# Connect.net
KiCad netlist of a schematic drawn in Altium Designer
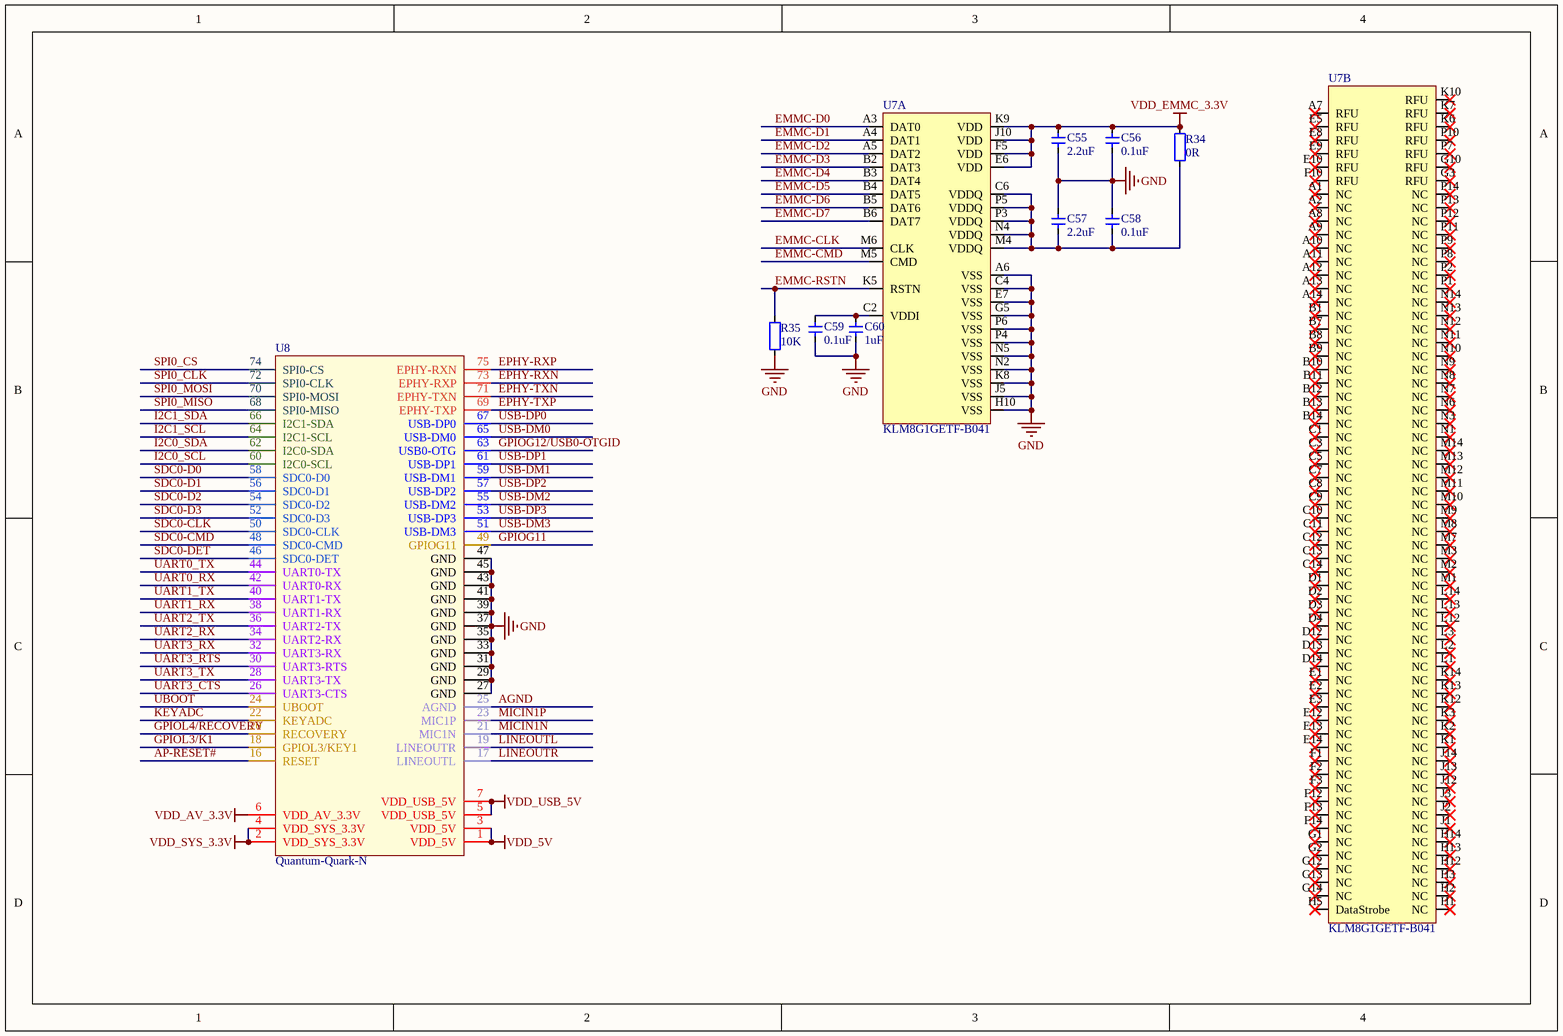
[diagram p0: Connect.SchDoc]

(export (version "E")
  (design (tool "Eeschema 10.0.6"))
  (components
    (comp (ref "C55")
      (value "2.2uF")
      (footprint "CAP_0402")
      (description "Capacitor")
      (libsource (lib "MyPcbLib") (part "电容-0402"))
    )
    (comp (ref "C56")
      (value "0.1uF")
      (footprint "CAP_0402")
      (description "Capacitor")
      (libsource (lib "MyPcbLib") (part "电容-0402"))
    )
    (comp (ref "C57")
      (value "2.2uF")
      (footprint "CAP_0402")
      (description "Capacitor")
      (libsource (lib "MyPcbLib") (part "电容-0402"))
    )
    (comp (ref "C58")
      (value "0.1uF")
      (footprint "CAP_0402")
      (description "Capacitor")
      (libsource (lib "MyPcbLib") (part "电容-0402"))
    )
    (comp (ref "C59")
      (value "0.1uF")
      (footprint "CAP_0402")
      (description "Capacitor")
      (libsource (lib "MyPcbLib") (part "电容-0402"))
    )
    (comp (ref "C60")
      (value "1uF")
      (footprint "CAP_0402")
      (description "Capacitor")
      (libsource (lib "MyPcbLib") (part "电容-0402"))
    )
    (comp (ref "R34")
      (value "0R")
      (footprint "RES_0402")
      (description "Resistor")
      (libsource (lib "MyPcbLib") (part "电阻-0402"))
    )
    (comp (ref "R35")
      (value "10K")
      (footprint "RES_0402")
      (description "Resistor")
      (libsource (lib "") (part "电阻-0402_1"))
    )
    (comp (ref "U7")
      (value "KLM8G1GETF-B041")
      (footprint "FBGA153")
      (description "8GB三星EMMC芯片")
      (libsource (lib "MxM") (part "EMMC"))
    )
    (comp (ref "U8")
      (value "Quantum-Quark-N")
      (footprint "M.2")
      (libsource (lib "MxM") (part "Quantum-Quark-N"))
    )
  )
  (nets
    (net (code "1") (name "/AGND") (class "Default")
      (node (ref "U8") (pin "25") (pinfunction "AGND_25") (pintype "passive"))
    )
    (net (code "2") (name "/AP-RESET#") (class "Default")
      (node (ref "U8") (pin "16") (pinfunction "RESET_16") (pintype "passive"))
    )
    (net (code "3") (name "/EMMC-CLK") (class "Default")
      (node (ref "U7") (pin "M6") (pinfunction "CLK_M6") (pintype "passive"))
    )
    (net (code "4") (name "/EMMC-CMD") (class "Default")
      (node (ref "U7") (pin "M5") (pinfunction "CMD_M5") (pintype "passive"))
    )
    (net (code "5") (name "/EMMC-D0") (class "Default")
      (node (ref "U7") (pin "A3") (pinfunction "DAT0_A3") (pintype "passive"))
    )
    (net (code "6") (name "/EMMC-D1") (class "Default")
      (node (ref "U7") (pin "A4") (pinfunction "DAT1_A4") (pintype "passive"))
    )
    (net (code "7") (name "/EMMC-D2") (class "Default")
      (node (ref "U7") (pin "A5") (pinfunction "DAT2_A5") (pintype "passive"))
    )
    (net (code "8") (name "/EMMC-D3") (class "Default")
      (node (ref "U7") (pin "B2") (pinfunction "DAT3_B2") (pintype "passive"))
    )
    (net (code "9") (name "/EMMC-D4") (class "Default")
      (node (ref "U7") (pin "B3") (pinfunction "DAT4_B3") (pintype "passive"))
    )
    (net (code "10") (name "/EMMC-D5") (class "Default")
      (node (ref "U7") (pin "B4") (pinfunction "DAT5_B4") (pintype "passive"))
    )
    (net (code "11") (name "/EMMC-D6") (class "Default")
      (node (ref "U7") (pin "B5") (pinfunction "DAT6_B5") (pintype "passive"))
    )
    (net (code "12") (name "/EMMC-D7") (class "Default")
      (node (ref "U7") (pin "B6") (pinfunction "DAT7_B6") (pintype "passive"))
    )
    (net (code "13") (name "/EMMC-RSTN") (class "Default")
      (node (ref "R35") (pin "2") (pinfunction "2_2") (pintype "passive"))
      (node (ref "U7") (pin "K5") (pinfunction "RSTN_K5") (pintype "passive"))
    )
    (net (code "14") (name "/EPHY-RXN") (class "Default")
      (node (ref "U8") (pin "73") (pinfunction "EPHY-RXP_73") (pintype "passive"))
    )
    (net (code "15") (name "/EPHY-RXP") (class "Default")
      (node (ref "U8") (pin "75") (pinfunction "EPHY-RXN_75") (pintype "passive"))
    )
    (net (code "16") (name "/EPHY-TXN") (class "Default")
      (node (ref "U8") (pin "71") (pinfunction "EPHY-TXN_71") (pintype "passive"))
    )
    (net (code "17") (name "/EPHY-TXP") (class "Default")
      (node (ref "U8") (pin "69") (pinfunction "EPHY-TXP_69") (pintype "passive"))
    )
    (net (code "18") (name "/GPIOG11") (class "Default")
      (node (ref "U8") (pin "49") (pinfunction "GPIOG11_49") (pintype "passive"))
    )
    (net (code "19") (name "/GPIOG12{slash}USB0-OTGID") (class "Default")
      (node (ref "U8") (pin "63") (pinfunction "USB0-OTG_63") (pintype "passive"))
    )
    (net (code "20") (name "/GPIOL3{slash}K1") (class "Default")
      (node (ref "U8") (pin "18") (pinfunction "GPIOL3/KEY1_18") (pintype "passive"))
    )
    (net (code "21") (name "/GPIOL4{slash}RECOVERY") (class "Default")
      (node (ref "U8") (pin "20") (pinfunction "RECOVERY_20") (pintype "passive"))
    )
    (net (code "22") (name "/I2C0_SCL") (class "Default")
      (node (ref "U8") (pin "60") (pinfunction "I2C0-SCL_60") (pintype "passive"))
    )
    (net (code "23") (name "/I2C0_SDA") (class "Default")
      (node (ref "U8") (pin "62") (pinfunction "I2C0-SDA_62") (pintype "passive"))
    )
    (net (code "24") (name "/I2C1_SCL") (class "Default")
      (node (ref "U8") (pin "64") (pinfunction "I2C1-SCL_64") (pintype "passive"))
    )
    (net (code "25") (name "/I2C1_SDA") (class "Default")
      (node (ref "U8") (pin "66") (pinfunction "I2C1-SDA_66") (pintype "passive"))
    )
    (net (code "26") (name "/KEYADC") (class "Default")
      (node (ref "U8") (pin "22") (pinfunction "KEYADC_22") (pintype "passive"))
    )
    (net (code "27") (name "/LINEOUTL") (class "Default")
      (node (ref "U8") (pin "19") (pinfunction "LINEOUTR_19") (pintype "passive"))
    )
    (net (code "28") (name "/LINEOUTR") (class "Default")
      (node (ref "U8") (pin "17") (pinfunction "LINEOUTL_17") (pintype "passive"))
    )
    (net (code "29") (name "/MICIN1N") (class "Default")
      (node (ref "U8") (pin "21") (pinfunction "MIC1N_21") (pintype "passive"))
    )
    (net (code "30") (name "/MICIN1P") (class "Default")
      (node (ref "U8") (pin "23") (pinfunction "MIC1P_23") (pintype "passive"))
    )
    (net (code "31") (name "/SDC0-CLK") (class "Default")
      (node (ref "U8") (pin "50") (pinfunction "SDC0-CLK_50") (pintype "passive"))
    )
    (net (code "32") (name "/SDC0-CMD") (class "Default")
      (node (ref "U8") (pin "48") (pinfunction "SDC0-CMD_48") (pintype "passive"))
    )
    (net (code "33") (name "/SDC0-D0") (class "Default")
      (node (ref "U8") (pin "58") (pinfunction "SDC0-D0_58") (pintype "passive"))
    )
    (net (code "34") (name "/SDC0-D1") (class "Default")
      (node (ref "U8") (pin "56") (pinfunction "SDC0-D1_56") (pintype "passive"))
    )
    (net (code "35") (name "/SDC0-D2") (class "Default")
      (node (ref "U8") (pin "54") (pinfunction "SDC0-D2_54") (pintype "passive"))
    )
    (net (code "36") (name "/SDC0-D3") (class "Default")
      (node (ref "U8") (pin "52") (pinfunction "SDC0-D3_52") (pintype "passive"))
    )
    (net (code "37") (name "/SDC0-DET") (class "Default")
      (node (ref "U8") (pin "46") (pinfunction "SDC0-DET_46") (pintype "passive"))
    )
    (net (code "38") (name "/SPI0_CLK") (class "Default")
      (node (ref "U8") (pin "72") (pinfunction "SPI0-CLK_72") (pintype "passive"))
    )
    (net (code "39") (name "/SPI0_CS") (class "Default")
      (node (ref "U8") (pin "74") (pinfunction "SPI0-CS_74") (pintype "passive"))
    )
    (net (code "40") (name "/SPI0_MISO") (class "Default")
      (node (ref "U8") (pin "68") (pinfunction "SPI0-MISO_68") (pintype "passive"))
    )
    (net (code "41") (name "/SPI0_MOSI") (class "Default")
      (node (ref "U8") (pin "70") (pinfunction "SPI0-MOSI_70") (pintype "passive"))
    )
    (net (code "42") (name "/UART0_RX") (class "Default")
      (node (ref "U8") (pin "42") (pinfunction "UART0-RX_42") (pintype "passive"))
    )
    (net (code "43") (name "/UART0_TX") (class "Default")
      (node (ref "U8") (pin "44") (pinfunction "UART0-TX_44") (pintype "passive"))
    )
    (net (code "44") (name "/UART1_RX") (class "Default")
      (node (ref "U8") (pin "38") (pinfunction "UART1-RX_38") (pintype "passive"))
    )
    (net (code "45") (name "/UART1_TX") (class "Default")
      (node (ref "U8") (pin "40") (pinfunction "UART1-TX_40") (pintype "passive"))
    )
    (net (code "46") (name "/UART2_RX") (class "Default")
      (node (ref "U8") (pin "34") (pinfunction "UART2-RX_34") (pintype "passive"))
    )
    (net (code "47") (name "/UART2_TX") (class "Default")
      (node (ref "U8") (pin "36") (pinfunction "UART2-TX_36") (pintype "passive"))
    )
    (net (code "48") (name "/UART3_CTS") (class "Default")
      (node (ref "U8") (pin "26") (pinfunction "UART3-CTS_26") (pintype "passive"))
    )
    (net (code "49") (name "/UART3_RTS") (class "Default")
      (node (ref "U8") (pin "30") (pinfunction "UART3-RTS_30") (pintype "passive"))
    )
    (net (code "50") (name "/UART3_RX") (class "Default")
      (node (ref "U8") (pin "32") (pinfunction "UART3-RX_32") (pintype "passive"))
    )
    (net (code "51") (name "/UART3_TX") (class "Default")
      (node (ref "U8") (pin "28") (pinfunction "UART3-TX_28") (pintype "passive"))
    )
    (net (code "52") (name "/UBOOT") (class "Default")
      (node (ref "U8") (pin "24") (pinfunction "UBOOT_24") (pintype "passive"))
    )
    (net (code "53") (name "/USB-DM0") (class "Default")
      (node (ref "U8") (pin "65") (pinfunction "USB-DM0_65") (pintype "passive"))
    )
    (net (code "54") (name "/USB-DM1") (class "Default")
      (node (ref "U8") (pin "59") (pinfunction "USB-DM1_59") (pintype "passive"))
    )
    (net (code "55") (name "/USB-DM2") (class "Default")
      (node (ref "U8") (pin "55") (pinfunction "USB-DM2_55") (pintype "passive"))
    )
    (net (code "56") (name "/USB-DM3") (class "Default")
      (node (ref "U8") (pin "51") (pinfunction "USB-DM3_51") (pintype "passive"))
    )
    (net (code "57") (name "/USB-DP0") (class "Default")
      (node (ref "U8") (pin "67") (pinfunction "USB-DP0_67") (pintype "passive"))
    )
    (net (code "58") (name "/USB-DP1") (class "Default")
      (node (ref "U8") (pin "61") (pinfunction "USB-DP1_61") (pintype "passive"))
    )
    (net (code "59") (name "/USB-DP2") (class "Default")
      (node (ref "U8") (pin "57") (pinfunction "USB-DP2_57") (pintype "passive"))
    )
    (net (code "60") (name "/USB-DP3") (class "Default")
      (node (ref "U8") (pin "53") (pinfunction "USB-DP3_53") (pintype "passive"))
    )
    (net (code "61") (name "GND") (class "Default")
      (node (ref "C55") (pin "1") (pinfunction "1_1") (pintype "passive"))
      (node (ref "C56") (pin "1") (pinfunction "1_1") (pintype "passive"))
      (node (ref "C57") (pin "2") (pinfunction "2_2") (pintype "passive"))
      (node (ref "C58") (pin "2") (pinfunction "2_2") (pintype "passive"))
      (node (ref "C59") (pin "1") (pinfunction "1_1") (pintype "passive"))
      (node (ref "C60") (pin "1") (pinfunction "1_1") (pintype "passive"))
      (node (ref "R35") (pin "1") (pinfunction "1_1") (pintype "passive"))
      (node (ref "U7") (pin "A6") (pinfunction "VSS_A6") (pintype "passive"))
      (node (ref "U7") (pin "C4") (pinfunction "VSS_C4") (pintype "passive"))
      (node (ref "U7") (pin "E7") (pinfunction "VSS_E7") (pintype "passive"))
      (node (ref "U7") (pin "G5") (pinfunction "VSS_G5") (pintype "passive"))
      (node (ref "U7") (pin "H10") (pinfunction "VSS_H10") (pintype "passive"))
      (node (ref "U7") (pin "J5") (pinfunction "VSS_J5") (pintype "passive"))
      (node (ref "U7") (pin "K8") (pinfunction "VSS_K8") (pintype "passive"))
      (node (ref "U7") (pin "N2") (pinfunction "VSS_N2") (pintype "passive"))
      (node (ref "U7") (pin "N5") (pinfunction "VSS_N5") (pintype "passive"))
      (node (ref "U7") (pin "P4") (pinfunction "VSS_P4") (pintype "passive"))
      (node (ref "U7") (pin "P6") (pinfunction "VSS_P6") (pintype "passive"))
      (node (ref "U8") (pin "27") (pinfunction "GND_27") (pintype "passive"))
      (node (ref "U8") (pin "29") (pinfunction "GND_29") (pintype "passive"))
      (node (ref "U8") (pin "31") (pinfunction "GND_31") (pintype "passive"))
      (node (ref "U8") (pin "33") (pinfunction "GND_33") (pintype "passive"))
      (node (ref "U8") (pin "35") (pinfunction "GND_35") (pintype "passive"))
      (node (ref "U8") (pin "37") (pinfunction "GND_37") (pintype "passive"))
      (node (ref "U8") (pin "39") (pinfunction "GND_39") (pintype "passive"))
      (node (ref "U8") (pin "41") (pinfunction "GND_41") (pintype "passive"))
      (node (ref "U8") (pin "43") (pinfunction "GND_43") (pintype "passive"))
      (node (ref "U8") (pin "45") (pinfunction "GND_45") (pintype "passive"))
      (node (ref "U8") (pin "47") (pinfunction "GND_47") (pintype "passive"))
    )
    (net (code "62") (name "Net-(C57-Pad1)") (class "Default")
      (node (ref "C57") (pin "1") (pinfunction "1_1") (pintype "passive"))
      (node (ref "C58") (pin "1") (pinfunction "1_1") (pintype "passive"))
      (node (ref "R34") (pin "2") (pinfunction "2_2") (pintype "passive"))
      (node (ref "U7") (pin "C6") (pinfunction "VDDQ_C6") (pintype "passive"))
      (node (ref "U7") (pin "M4") (pinfunction "VDDQ_M4") (pintype "passive"))
      (node (ref "U7") (pin "N4") (pinfunction "VDDQ_N4") (pintype "passive"))
      (node (ref "U7") (pin "P3") (pinfunction "VDDQ_P3") (pintype "passive"))
      (node (ref "U7") (pin "P5") (pinfunction "VDDQ_P5") (pintype "passive"))
    )
    (net (code "63") (name "Net-(U7A-VDDI)") (class "Default")
      (node (ref "C59") (pin "2") (pinfunction "2_2") (pintype "passive"))
      (node (ref "C60") (pin "2") (pinfunction "2_2") (pintype "passive"))
      (node (ref "U7") (pin "C2") (pinfunction "VDDI_C2") (pintype "passive"))
    )
    (net (code "64") (name "VDD_5V") (class "Default")
      (node (ref "U8") (pin "1") (pinfunction "VDD_5V_1") (pintype "passive"))
      (node (ref "U8") (pin "3") (pinfunction "VDD_5V_3") (pintype "passive"))
    )
    (net (code "65") (name "VDD_AV_3.3V") (class "Default")
      (node (ref "U8") (pin "6") (pinfunction "VDD_AV_3.3V_6") (pintype "passive"))
    )
    (net (code "66") (name "VDD_EMMC_3.3V") (class "Default")
      (node (ref "C55") (pin "2") (pinfunction "2_2") (pintype "passive"))
      (node (ref "C56") (pin "2") (pinfunction "2_2") (pintype "passive"))
      (node (ref "R34") (pin "1") (pinfunction "1_1") (pintype "passive"))
      (node (ref "U7") (pin "E6") (pinfunction "VDD_E6") (pintype "passive"))
      (node (ref "U7") (pin "F5") (pinfunction "VDD_F5") (pintype "passive"))
      (node (ref "U7") (pin "J10") (pinfunction "VDD_J10") (pintype "passive"))
      (node (ref "U7") (pin "K9") (pinfunction "VDD_K9") (pintype "passive"))
    )
    (net (code "67") (name "VDD_SYS_3.3V") (class "Default")
      (node (ref "U8") (pin "2") (pinfunction "VDD_SYS_3.3V_2") (pintype "passive"))
      (node (ref "U8") (pin "4") (pinfunction "VDD_SYS_3.3V_4") (pintype "passive"))
    )
    (net (code "68") (name "VDD_USB_5V") (class "Default")
      (node (ref "U8") (pin "5") (pinfunction "VDD_USB_5V_5") (pintype "passive"))
      (node (ref "U8") (pin "7") (pinfunction "VDD_USB_5V_7") (pintype "passive"))
    )
    (net (code "69") (name "unconnected-(U7B-DataStrobe-PadH5)") (class "Default")
      (node (ref "U7") (pin "H5") (pinfunction "DataStrobe_H5") (pintype "passive+no_connect"))
    )
    (net (code "70") (name "unconnected-(U7B-NC-PadA1)") (class "Default")
      (node (ref "U7") (pin "A1") (pinfunction "NC_A1") (pintype "passive+no_connect"))
    )
    (net (code "71") (name "unconnected-(U7B-NC-PadA2)") (class "Default")
      (node (ref "U7") (pin "A2") (pinfunction "NC_A2") (pintype "passive+no_connect"))
    )
    (net (code "72") (name "unconnected-(U7B-NC-PadA8)") (class "Default")
      (node (ref "U7") (pin "A8") (pinfunction "NC_A8") (pintype "passive+no_connect"))
    )
    (net (code "73") (name "unconnected-(U7B-NC-PadA9)") (class "Default")
      (node (ref "U7") (pin "A9") (pinfunction "NC_A9") (pintype "passive+no_connect"))
    )
    (net (code "74") (name "unconnected-(U7B-NC-PadA10)") (class "Default")
      (node (ref "U7") (pin "A10") (pinfunction "NC_A10") (pintype "passive+no_connect"))
    )
    (net (code "75") (name "unconnected-(U7B-NC-PadA11)") (class "Default")
      (node (ref "U7") (pin "A11") (pinfunction "NC_A11") (pintype "passive+no_connect"))
    )
    (net (code "76") (name "unconnected-(U7B-NC-PadA12)") (class "Default")
      (node (ref "U7") (pin "A12") (pinfunction "NC_A12") (pintype "passive+no_connect"))
    )
    (net (code "77") (name "unconnected-(U7B-NC-PadA13)") (class "Default")
      (node (ref "U7") (pin "A13") (pinfunction "NC_A13") (pintype "passive+no_connect"))
    )
    (net (code "78") (name "unconnected-(U7B-NC-PadA14)") (class "Default")
      (node (ref "U7") (pin "A14") (pinfunction "NC_A14") (pintype "passive+no_connect"))
    )
    (net (code "79") (name "unconnected-(U7B-NC-PadB1)") (class "Default")
      (node (ref "U7") (pin "B1") (pinfunction "NC_B1") (pintype "passive+no_connect"))
    )
    (net (code "80") (name "unconnected-(U7B-NC-PadB7)") (class "Default")
      (node (ref "U7") (pin "B7") (pinfunction "NC_B7") (pintype "passive+no_connect"))
    )
    (net (code "81") (name "unconnected-(U7B-NC-PadB8)") (class "Default")
      (node (ref "U7") (pin "B8") (pinfunction "NC_B8") (pintype "passive+no_connect"))
    )
    (net (code "82") (name "unconnected-(U7B-NC-PadB9)") (class "Default")
      (node (ref "U7") (pin "B9") (pinfunction "NC_B9") (pintype "passive+no_connect"))
    )
    (net (code "83") (name "unconnected-(U7B-NC-PadB10)") (class "Default")
      (node (ref "U7") (pin "B10") (pinfunction "NC_B10") (pintype "passive+no_connect"))
    )
    (net (code "84") (name "unconnected-(U7B-NC-PadB11)") (class "Default")
      (node (ref "U7") (pin "B11") (pinfunction "NC_B11") (pintype "passive+no_connect"))
    )
    (net (code "85") (name "unconnected-(U7B-NC-PadB12)") (class "Default")
      (node (ref "U7") (pin "B12") (pinfunction "NC_B12") (pintype "passive+no_connect"))
    )
    (net (code "86") (name "unconnected-(U7B-NC-PadB13)") (class "Default")
      (node (ref "U7") (pin "B13") (pinfunction "NC_B13") (pintype "passive+no_connect"))
    )
    (net (code "87") (name "unconnected-(U7B-NC-PadB14)") (class "Default")
      (node (ref "U7") (pin "B14") (pinfunction "NC_B14") (pintype "passive+no_connect"))
    )
    (net (code "88") (name "unconnected-(U7B-NC-PadC1)") (class "Default")
      (node (ref "U7") (pin "C1") (pinfunction "NC_C1") (pintype "passive+no_connect"))
    )
    (net (code "89") (name "unconnected-(U7B-NC-PadC3)") (class "Default")
      (node (ref "U7") (pin "C3") (pinfunction "NC_C3") (pintype "passive+no_connect"))
    )
    (net (code "90") (name "unconnected-(U7B-NC-PadC5)") (class "Default")
      (node (ref "U7") (pin "C5") (pinfunction "NC_C5") (pintype "passive+no_connect"))
    )
    (net (code "91") (name "unconnected-(U7B-NC-PadC7)") (class "Default")
      (node (ref "U7") (pin "C7") (pinfunction "NC_C7") (pintype "passive+no_connect"))
    )
    (net (code "92") (name "unconnected-(U7B-NC-PadC8)") (class "Default")
      (node (ref "U7") (pin "C8") (pinfunction "NC_C8") (pintype "passive+no_connect"))
    )
    (net (code "93") (name "unconnected-(U7B-NC-PadC9)") (class "Default")
      (node (ref "U7") (pin "C9") (pinfunction "NC_C9") (pintype "passive+no_connect"))
    )
    (net (code "94") (name "unconnected-(U7B-NC-PadC10)") (class "Default")
      (node (ref "U7") (pin "C10") (pinfunction "NC_C10") (pintype "passive+no_connect"))
    )
    (net (code "95") (name "unconnected-(U7B-NC-PadC11)") (class "Default")
      (node (ref "U7") (pin "C11") (pinfunction "NC_C11") (pintype "passive+no_connect"))
    )
    (net (code "96") (name "unconnected-(U7B-NC-PadC12)") (class "Default")
      (node (ref "U7") (pin "C12") (pinfunction "NC_C12") (pintype "passive+no_connect"))
    )
    (net (code "97") (name "unconnected-(U7B-NC-PadC13)") (class "Default")
      (node (ref "U7") (pin "C13") (pinfunction "NC_C13") (pintype "passive+no_connect"))
    )
    (net (code "98") (name "unconnected-(U7B-NC-PadC14)") (class "Default")
      (node (ref "U7") (pin "C14") (pinfunction "NC_C14") (pintype "passive+no_connect"))
    )
    (net (code "99") (name "unconnected-(U7B-NC-PadD1)") (class "Default")
      (node (ref "U7") (pin "D1") (pinfunction "NC_D1") (pintype "passive+no_connect"))
    )
    (net (code "100") (name "unconnected-(U7B-NC-PadD2)") (class "Default")
      (node (ref "U7") (pin "D2") (pinfunction "NC_D2") (pintype "passive+no_connect"))
    )
    (net (code "101") (name "unconnected-(U7B-NC-PadD3)") (class "Default")
      (node (ref "U7") (pin "D3") (pinfunction "NC_D3") (pintype "passive+no_connect"))
    )
    (net (code "102") (name "unconnected-(U7B-NC-PadD4)") (class "Default")
      (node (ref "U7") (pin "D4") (pinfunction "NC_D4") (pintype "passive+no_connect"))
    )
    (net (code "103") (name "unconnected-(U7B-NC-PadD12)") (class "Default")
      (node (ref "U7") (pin "D12") (pinfunction "NC_D12") (pintype "passive+no_connect"))
    )
    (net (code "104") (name "unconnected-(U7B-NC-PadD13)") (class "Default")
      (node (ref "U7") (pin "D13") (pinfunction "NC_D13") (pintype "passive+no_connect"))
    )
    (net (code "105") (name "unconnected-(U7B-NC-PadD14)") (class "Default")
      (node (ref "U7") (pin "D14") (pinfunction "NC_D14") (pintype "passive+no_connect"))
    )
    (net (code "106") (name "unconnected-(U7B-NC-PadE1)") (class "Default")
      (node (ref "U7") (pin "E1") (pinfunction "NC_E1") (pintype "passive+no_connect"))
    )
    (net (code "107") (name "unconnected-(U7B-NC-PadE2)") (class "Default")
      (node (ref "U7") (pin "E2") (pinfunction "NC_E2") (pintype "passive+no_connect"))
    )
    (net (code "108") (name "unconnected-(U7B-NC-PadE3)") (class "Default")
      (node (ref "U7") (pin "E3") (pinfunction "NC_E3") (pintype "passive+no_connect"))
    )
    (net (code "109") (name "unconnected-(U7B-NC-PadE12)") (class "Default")
      (node (ref "U7") (pin "E12") (pinfunction "NC_E12") (pintype "passive+no_connect"))
    )
    (net (code "110") (name "unconnected-(U7B-NC-PadE13)") (class "Default")
      (node (ref "U7") (pin "E13") (pinfunction "NC_E13") (pintype "passive+no_connect"))
    )
    (net (code "111") (name "unconnected-(U7B-NC-PadE14)") (class "Default")
      (node (ref "U7") (pin "E14") (pinfunction "NC_E14") (pintype "passive+no_connect"))
    )
    (net (code "112") (name "unconnected-(U7B-NC-PadF1)") (class "Default")
      (node (ref "U7") (pin "F1") (pinfunction "NC_F1") (pintype "passive+no_connect"))
    )
    (net (code "113") (name "unconnected-(U7B-NC-PadF2)") (class "Default")
      (node (ref "U7") (pin "F2") (pinfunction "NC_F2") (pintype "passive+no_connect"))
    )
    (net (code "114") (name "unconnected-(U7B-NC-PadF3)") (class "Default")
      (node (ref "U7") (pin "F3") (pinfunction "NC_F3") (pintype "passive+no_connect"))
    )
    (net (code "115") (name "unconnected-(U7B-NC-PadF12)") (class "Default")
      (node (ref "U7") (pin "F12") (pinfunction "NC_F12") (pintype "passive+no_connect"))
    )
    (net (code "116") (name "unconnected-(U7B-NC-PadF13)") (class "Default")
      (node (ref "U7") (pin "F13") (pinfunction "NC_F13") (pintype "passive+no_connect"))
    )
    (net (code "117") (name "unconnected-(U7B-NC-PadF14)") (class "Default")
      (node (ref "U7") (pin "F14") (pinfunction "NC_F14") (pintype "passive+no_connect"))
    )
    (net (code "118") (name "unconnected-(U7B-NC-PadG1)") (class "Default")
      (node (ref "U7") (pin "G1") (pinfunction "NC_G1") (pintype "passive+no_connect"))
    )
    (net (code "119") (name "unconnected-(U7B-NC-PadG2)") (class "Default")
      (node (ref "U7") (pin "G2") (pinfunction "NC_G2") (pintype "passive+no_connect"))
    )
    (net (code "120") (name "unconnected-(U7B-NC-PadG12)") (class "Default")
      (node (ref "U7") (pin "G12") (pinfunction "NC_G12") (pintype "passive+no_connect"))
    )
    (net (code "121") (name "unconnected-(U7B-NC-PadG13)") (class "Default")
      (node (ref "U7") (pin "G13") (pinfunction "NC_G13") (pintype "passive+no_connect"))
    )
    (net (code "122") (name "unconnected-(U7B-NC-PadG14)") (class "Default")
      (node (ref "U7") (pin "G14") (pinfunction "NC_G14") (pintype "passive+no_connect"))
    )
    (net (code "123") (name "unconnected-(U7B-NC-PadH1)") (class "Default")
      (node (ref "U7") (pin "H1") (pinfunction "NC_H1") (pintype "passive+no_connect"))
    )
    (net (code "124") (name "unconnected-(U7B-NC-PadH2)") (class "Default")
      (node (ref "U7") (pin "H2") (pinfunction "NC_H2") (pintype "passive+no_connect"))
    )
    (net (code "125") (name "unconnected-(U7B-NC-PadH3)") (class "Default")
      (node (ref "U7") (pin "H3") (pinfunction "NC_H3") (pintype "passive+no_connect"))
    )
    (net (code "126") (name "unconnected-(U7B-NC-PadH12)") (class "Default")
      (node (ref "U7") (pin "H12") (pinfunction "NC_H12") (pintype "passive+no_connect"))
    )
    (net (code "127") (name "unconnected-(U7B-NC-PadH13)") (class "Default")
      (node (ref "U7") (pin "H13") (pinfunction "NC_H13") (pintype "passive+no_connect"))
    )
    (net (code "128") (name "unconnected-(U7B-NC-PadH14)") (class "Default")
      (node (ref "U7") (pin "H14") (pinfunction "NC_H14") (pintype "passive+no_connect"))
    )
    (net (code "129") (name "unconnected-(U7B-NC-PadJ1)") (class "Default")
      (node (ref "U7") (pin "J1") (pinfunction "NC_J1") (pintype "passive+no_connect"))
    )
    (net (code "130") (name "unconnected-(U7B-NC-PadJ2)") (class "Default")
      (node (ref "U7") (pin "J2") (pinfunction "NC_J2") (pintype "passive+no_connect"))
    )
    (net (code "131") (name "unconnected-(U7B-NC-PadJ3)") (class "Default")
      (node (ref "U7") (pin "J3") (pinfunction "NC_J3") (pintype "passive+no_connect"))
    )
    (net (code "132") (name "unconnected-(U7B-NC-PadJ12)") (class "Default")
      (node (ref "U7") (pin "J12") (pinfunction "NC_J12") (pintype "passive+no_connect"))
    )
    (net (code "133") (name "unconnected-(U7B-NC-PadJ13)") (class "Default")
      (node (ref "U7") (pin "J13") (pinfunction "NC_J13") (pintype "passive+no_connect"))
    )
    (net (code "134") (name "unconnected-(U7B-NC-PadJ14)") (class "Default")
      (node (ref "U7") (pin "J14") (pinfunction "NC_J14") (pintype "passive+no_connect"))
    )
    (net (code "135") (name "unconnected-(U7B-NC-PadK1)") (class "Default")
      (node (ref "U7") (pin "K1") (pinfunction "NC_K1") (pintype "passive+no_connect"))
    )
    (net (code "136") (name "unconnected-(U7B-NC-PadK2)") (class "Default")
      (node (ref "U7") (pin "K2") (pinfunction "NC_K2") (pintype "passive+no_connect"))
    )
    (net (code "137") (name "unconnected-(U7B-NC-PadK3)") (class "Default")
      (node (ref "U7") (pin "K3") (pinfunction "NC_K3") (pintype "passive+no_connect"))
    )
    (net (code "138") (name "unconnected-(U7B-NC-PadK12)") (class "Default")
      (node (ref "U7") (pin "K12") (pinfunction "NC_K12") (pintype "passive+no_connect"))
    )
    (net (code "139") (name "unconnected-(U7B-NC-PadK13)") (class "Default")
      (node (ref "U7") (pin "K13") (pinfunction "NC_K13") (pintype "passive+no_connect"))
    )
    (net (code "140") (name "unconnected-(U7B-NC-PadK14)") (class "Default")
      (node (ref "U7") (pin "K14") (pinfunction "NC_K14") (pintype "passive+no_connect"))
    )
    (net (code "141") (name "unconnected-(U7B-NC-PadL1)") (class "Default")
      (node (ref "U7") (pin "L1") (pinfunction "NC_L1") (pintype "passive+no_connect"))
    )
    (net (code "142") (name "unconnected-(U7B-NC-PadL2)") (class "Default")
      (node (ref "U7") (pin "L2") (pinfunction "NC_L2") (pintype "passive+no_connect"))
    )
    (net (code "143") (name "unconnected-(U7B-NC-PadL3)") (class "Default")
      (node (ref "U7") (pin "L3") (pinfunction "NC_L3") (pintype "passive+no_connect"))
    )
    (net (code "144") (name "unconnected-(U7B-NC-PadL12)") (class "Default")
      (node (ref "U7") (pin "L12") (pinfunction "NC_L12") (pintype "passive+no_connect"))
    )
    (net (code "145") (name "unconnected-(U7B-NC-PadL13)") (class "Default")
      (node (ref "U7") (pin "L13") (pinfunction "NC_L13") (pintype "passive+no_connect"))
    )
    (net (code "146") (name "unconnected-(U7B-NC-PadL14)") (class "Default")
      (node (ref "U7") (pin "L14") (pinfunction "NC_L14") (pintype "passive+no_connect"))
    )
    (net (code "147") (name "unconnected-(U7B-NC-PadM1)") (class "Default")
      (node (ref "U7") (pin "M1") (pinfunction "NC_M1") (pintype "passive+no_connect"))
    )
    (net (code "148") (name "unconnected-(U7B-NC-PadM2)") (class "Default")
      (node (ref "U7") (pin "M2") (pinfunction "NC_M2") (pintype "passive+no_connect"))
    )
    (net (code "149") (name "unconnected-(U7B-NC-PadM3)") (class "Default")
      (node (ref "U7") (pin "M3") (pinfunction "NC_M3") (pintype "passive+no_connect"))
    )
    (net (code "150") (name "unconnected-(U7B-NC-PadM7)") (class "Default")
      (node (ref "U7") (pin "M7") (pinfunction "NC_M7") (pintype "passive+no_connect"))
    )
    (net (code "151") (name "unconnected-(U7B-NC-PadM8)") (class "Default")
      (node (ref "U7") (pin "M8") (pinfunction "NC_M8") (pintype "passive+no_connect"))
    )
    (net (code "152") (name "unconnected-(U7B-NC-PadM9)") (class "Default")
      (node (ref "U7") (pin "M9") (pinfunction "NC_M9") (pintype "passive+no_connect"))
    )
    (net (code "153") (name "unconnected-(U7B-NC-PadM10)") (class "Default")
      (node (ref "U7") (pin "M10") (pinfunction "NC_M10") (pintype "passive+no_connect"))
    )
    (net (code "154") (name "unconnected-(U7B-NC-PadM11)") (class "Default")
      (node (ref "U7") (pin "M11") (pinfunction "NC_M11") (pintype "passive+no_connect"))
    )
    (net (code "155") (name "unconnected-(U7B-NC-PadM12)") (class "Default")
      (node (ref "U7") (pin "M12") (pinfunction "NC_M12") (pintype "passive+no_connect"))
    )
    (net (code "156") (name "unconnected-(U7B-NC-PadM13)") (class "Default")
      (node (ref "U7") (pin "M13") (pinfunction "NC_M13") (pintype "passive+no_connect"))
    )
    (net (code "157") (name "unconnected-(U7B-NC-PadM14)") (class "Default")
      (node (ref "U7") (pin "M14") (pinfunction "NC_M14") (pintype "passive+no_connect"))
    )
    (net (code "158") (name "unconnected-(U7B-NC-PadN1)") (class "Default")
      (node (ref "U7") (pin "N1") (pinfunction "NC_N1") (pintype "passive+no_connect"))
    )
    (net (code "159") (name "unconnected-(U7B-NC-PadN3)") (class "Default")
      (node (ref "U7") (pin "N3") (pinfunction "NC_N3") (pintype "passive+no_connect"))
    )
    (net (code "160") (name "unconnected-(U7B-NC-PadN6)") (class "Default")
      (node (ref "U7") (pin "N6") (pinfunction "NC_N6") (pintype "passive+no_connect"))
    )
    (net (code "161") (name "unconnected-(U7B-NC-PadN7)") (class "Default")
      (node (ref "U7") (pin "N7") (pinfunction "NC_N7") (pintype "passive+no_connect"))
    )
    (net (code "162") (name "unconnected-(U7B-NC-PadN8)") (class "Default")
      (node (ref "U7") (pin "N8") (pinfunction "NC_N8") (pintype "passive+no_connect"))
    )
    (net (code "163") (name "unconnected-(U7B-NC-PadN9)") (class "Default")
      (node (ref "U7") (pin "N9") (pinfunction "NC_N9") (pintype "passive+no_connect"))
    )
    (net (code "164") (name "unconnected-(U7B-NC-PadN10)") (class "Default")
      (node (ref "U7") (pin "N10") (pinfunction "NC_N10") (pintype "passive+no_connect"))
    )
    (net (code "165") (name "unconnected-(U7B-NC-PadN11)") (class "Default")
      (node (ref "U7") (pin "N11") (pinfunction "NC_N11") (pintype "passive+no_connect"))
    )
    (net (code "166") (name "unconnected-(U7B-NC-PadN12)") (class "Default")
      (node (ref "U7") (pin "N12") (pinfunction "NC_N12") (pintype "passive+no_connect"))
    )
    (net (code "167") (name "unconnected-(U7B-NC-PadN13)") (class "Default")
      (node (ref "U7") (pin "N13") (pinfunction "NC_N13") (pintype "passive+no_connect"))
    )
    (net (code "168") (name "unconnected-(U7B-NC-PadN14)") (class "Default")
      (node (ref "U7") (pin "N14") (pinfunction "NC_N14") (pintype "passive+no_connect"))
    )
    (net (code "169") (name "unconnected-(U7B-NC-PadP1)") (class "Default")
      (node (ref "U7") (pin "P1") (pinfunction "NC_P1") (pintype "passive+no_connect"))
    )
    (net (code "170") (name "unconnected-(U7B-NC-PadP2)") (class "Default")
      (node (ref "U7") (pin "P2") (pinfunction "NC_P2") (pintype "passive+no_connect"))
    )
    (net (code "171") (name "unconnected-(U7B-NC-PadP8)") (class "Default")
      (node (ref "U7") (pin "P8") (pinfunction "NC_P8") (pintype "passive+no_connect"))
    )
    (net (code "172") (name "unconnected-(U7B-NC-PadP9)") (class "Default")
      (node (ref "U7") (pin "P9") (pinfunction "NC_P9") (pintype "passive+no_connect"))
    )
    (net (code "173") (name "unconnected-(U7B-NC-PadP11)") (class "Default")
      (node (ref "U7") (pin "P11") (pinfunction "NC_P11") (pintype "passive+no_connect"))
    )
    (net (code "174") (name "unconnected-(U7B-NC-PadP12)") (class "Default")
      (node (ref "U7") (pin "P12") (pinfunction "NC_P12") (pintype "passive+no_connect"))
    )
    (net (code "175") (name "unconnected-(U7B-NC-PadP13)") (class "Default")
      (node (ref "U7") (pin "P13") (pinfunction "NC_P13") (pintype "passive+no_connect"))
    )
    (net (code "176") (name "unconnected-(U7B-NC-PadP14)") (class "Default")
      (node (ref "U7") (pin "P14") (pinfunction "NC_P14") (pintype "passive+no_connect"))
    )
    (net (code "177") (name "unconnected-(U7B-RFU-PadA7)") (class "Default")
      (node (ref "U7") (pin "A7") (pinfunction "RFU_A7") (pintype "passive+no_connect"))
    )
    (net (code "178") (name "unconnected-(U7B-RFU-PadE5)") (class "Default")
      (node (ref "U7") (pin "E5") (pinfunction "RFU_E5") (pintype "passive+no_connect"))
    )
    (net (code "179") (name "unconnected-(U7B-RFU-PadE8)") (class "Default")
      (node (ref "U7") (pin "E8") (pinfunction "RFU_E8") (pintype "passive+no_connect"))
    )
    (net (code "180") (name "unconnected-(U7B-RFU-PadE9)") (class "Default")
      (node (ref "U7") (pin "E9") (pinfunction "RFU_E9") (pintype "passive+no_connect"))
    )
    (net (code "181") (name "unconnected-(U7B-RFU-PadE10)") (class "Default")
      (node (ref "U7") (pin "E10") (pinfunction "RFU_E10") (pintype "passive+no_connect"))
    )
    (net (code "182") (name "unconnected-(U7B-RFU-PadF10)") (class "Default")
      (node (ref "U7") (pin "F10") (pinfunction "RFU_F10") (pintype "passive+no_connect"))
    )
    (net (code "183") (name "unconnected-(U7B-RFU-PadG3)") (class "Default")
      (node (ref "U7") (pin "G3") (pinfunction "RFU_G3") (pintype "passive+no_connect"))
    )
    (net (code "184") (name "unconnected-(U7B-RFU-PadG10)") (class "Default")
      (node (ref "U7") (pin "G10") (pinfunction "RFU_G10") (pintype "passive+no_connect"))
    )
    (net (code "185") (name "unconnected-(U7B-RFU-PadK6)") (class "Default")
      (node (ref "U7") (pin "K6") (pinfunction "RFU_K6") (pintype "passive+no_connect"))
    )
    (net (code "186") (name "unconnected-(U7B-RFU-PadK7)") (class "Default")
      (node (ref "U7") (pin "K7") (pinfunction "RFU_K7") (pintype "passive+no_connect"))
    )
    (net (code "187") (name "unconnected-(U7B-RFU-PadK10)") (class "Default")
      (node (ref "U7") (pin "K10") (pinfunction "RFU_K10") (pintype "passive+no_connect"))
    )
    (net (code "188") (name "unconnected-(U7B-RFU-PadP7)") (class "Default")
      (node (ref "U7") (pin "P7") (pinfunction "RFU_P7") (pintype "passive+no_connect"))
    )
    (net (code "189") (name "unconnected-(U7B-RFU-PadP10)") (class "Default")
      (node (ref "U7") (pin "P10") (pinfunction "RFU_P10") (pintype "passive+no_connect"))
    )
  )
)
